# Conn_pcb1.net
KiCad netlist of a schematic drawn in EAGLE
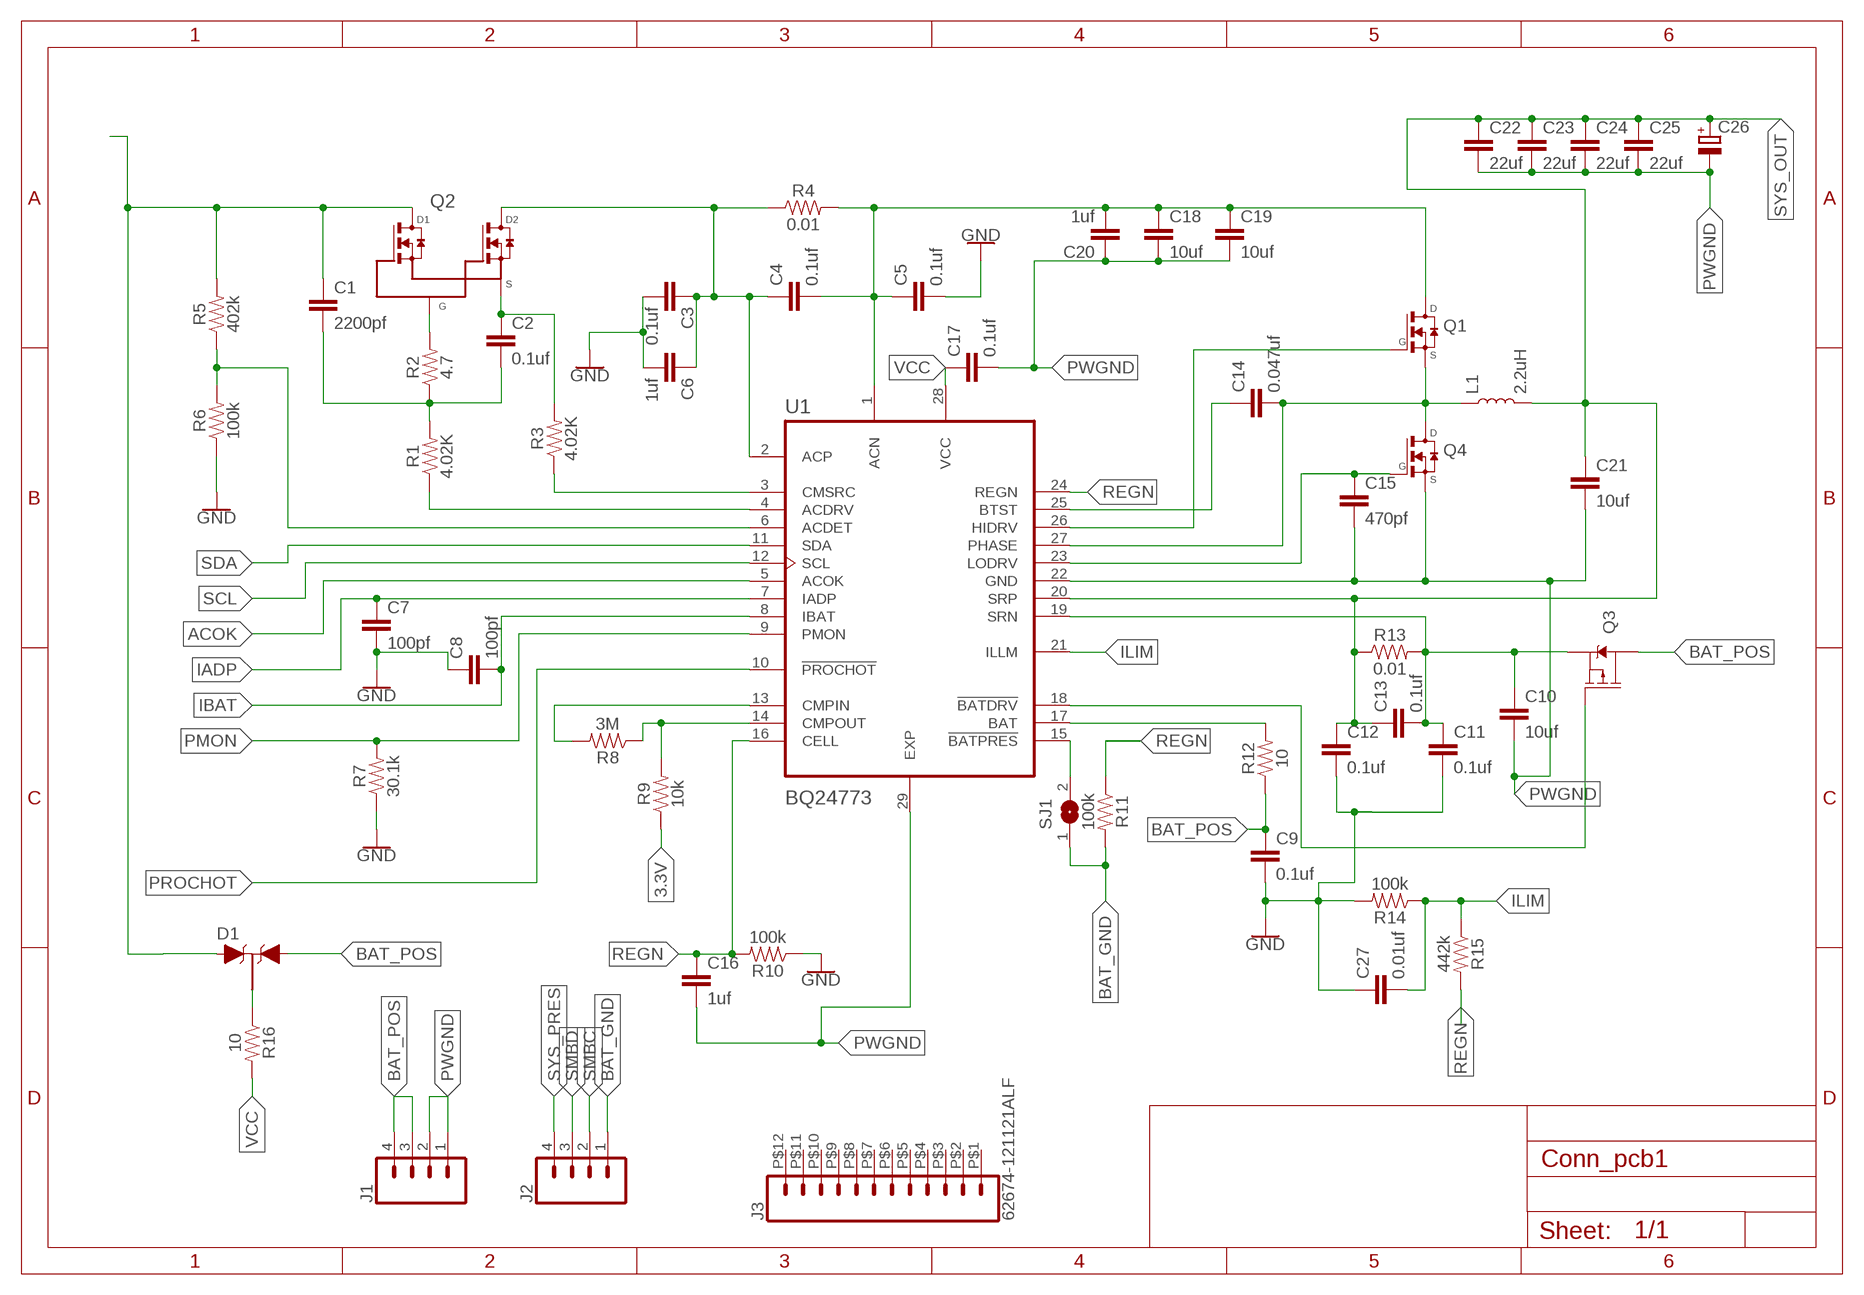
[diagram p0: schematic, sheet 1]

(export (version "E")
  (design (tool "Eeschema 10.0.6"))
  (components
    (comp (ref "C1")
      (value "2200pf")
      (footprint "eagle-import:CAPC1005X50")
      (libsource (lib "eagle-import") (part "CAP0402"))
    )
    (comp (ref "C2")
      (value "0.1uf")
      (footprint "eagle-import:CAPC1005X50")
      (libsource (lib "eagle-import") (part "CAP0402"))
    )
    (comp (ref "C3")
      (value "0.1uf")
      (footprint "eagle-import:CAPC1005X50")
      (libsource (lib "eagle-import") (part "CAP0402"))
    )
    (comp (ref "C4")
      (value "0.1uf")
      (footprint "eagle-import:CAPC1005X50")
      (libsource (lib "eagle-import") (part "CAP0402"))
    )
    (comp (ref "C5")
      (value "0.1uf")
      (footprint "eagle-import:CAPC1005X50")
      (libsource (lib "eagle-import") (part "CAP0402"))
    )
    (comp (ref "C6")
      (value "1uf")
      (footprint "eagle-import:CAPC1005X50")
      (libsource (lib "eagle-import") (part "CAP0402"))
    )
    (comp (ref "C7")
      (value "100pf")
      (footprint "eagle-import:CAPC1005X50")
      (libsource (lib "eagle-import") (part "CAP0402"))
    )
    (comp (ref "C8")
      (value "100pf")
      (footprint "eagle-import:CAPC1005X50")
      (libsource (lib "eagle-import") (part "CAP0402"))
    )
    (comp (ref "C9")
      (value "0.1uf")
      (footprint "eagle-import:CAPC1005X50")
      (libsource (lib "eagle-import") (part "CAP0402"))
    )
    (comp (ref "C10")
      (value "10uf")
      (footprint "eagle-import:C0805K")
      (libsource (lib "eagle-import") (part "C-EUC0805K"))
    )
    (comp (ref "C11")
      (value "0.1uf")
      (footprint "eagle-import:CAPC1005X50")
      (libsource (lib "eagle-import") (part "CAP0402"))
    )
    (comp (ref "C12")
      (value "0.1uf")
      (footprint "eagle-import:CAPC1005X50")
      (libsource (lib "eagle-import") (part "CAP0402"))
    )
    (comp (ref "C13")
      (value "0.1uf")
      (footprint "eagle-import:CAPC1005X50")
      (libsource (lib "eagle-import") (part "CAP0402"))
    )
    (comp (ref "C14")
      (value "0.047uf")
      (footprint "eagle-import:CAPC1005X50")
      (libsource (lib "eagle-import") (part "CAP0402"))
    )
    (comp (ref "C15")
      (value "470pf")
      (footprint "eagle-import:CAPC1005X50")
      (libsource (lib "eagle-import") (part "CAP0402"))
    )
    (comp (ref "C16")
      (value "1uf")
      (footprint "eagle-import:CAPC1005X50")
      (libsource (lib "eagle-import") (part "CAP0402"))
    )
    (comp (ref "C17")
      (value "0.1uf")
      (footprint "eagle-import:CAPC1005X50")
      (libsource (lib "eagle-import") (part "CAP0402"))
    )
    (comp (ref "C18")
      (value "10uf")
      (footprint "eagle-import:C0805K")
      (libsource (lib "eagle-import") (part "C-EUC0805K"))
    )
    (comp (ref "C19")
      (value "10uf")
      (footprint "eagle-import:C0805K")
      (libsource (lib "eagle-import") (part "C-EUC0805K"))
    )
    (comp (ref "C20")
      (value "1uf")
      (footprint "eagle-import:CAPC1005X50")
      (libsource (lib "eagle-import") (part "CAP0402"))
    )
    (comp (ref "C21")
      (value "10uf")
      (footprint "eagle-import:C0805K")
      (libsource (lib "eagle-import") (part "C-EUC0805K"))
    )
    (comp (ref "C22")
      (value "22uf")
      (footprint "eagle-import:C1206")
      (libsource (lib "eagle-import") (part "C-EUC1206"))
    )
    (comp (ref "C23")
      (value "22uf")
      (footprint "eagle-import:C1206")
      (libsource (lib "eagle-import") (part "C-EUC1206"))
    )
    (comp (ref "C24")
      (value "22uf")
      (footprint "eagle-import:C1206")
      (libsource (lib "eagle-import") (part "C-EUC1206"))
    )
    (comp (ref "C25")
      (value "22uf")
      (footprint "eagle-import:C1206")
      (libsource (lib "eagle-import") (part "C-EUC1206"))
    )
    (comp (ref "C26")
      (value "CPOL-EUF")
      (footprint "eagle-import:PANASONIC_F")
      (libsource (lib "eagle-import") (part "CPOL-EUF"))
    )
    (comp (ref "C27")
      (value "0.01uf")
      (footprint "eagle-import:CAPC1005X50")
      (libsource (lib "eagle-import") (part "CAP0402"))
    )
    (comp (ref "D1")
      (value "BAT54C-7-F")
      (footprint "eagle-import:SOT95P235X110-3")
      (libsource (lib "eagle-import") (part "BAT54C-7-F"))
    )
    (comp (ref "J1")
      (value "CONN_041.3")
      (footprint "eagle-import:1X04_NO_SILK_1.3")
      (libsource (lib "eagle-import") (part "CONN_041.3"))
    )
    (comp (ref "J2")
      (value "CONN_041.3")
      (footprint "eagle-import:1X04_NO_SILK_1.3")
      (libsource (lib "eagle-import") (part "CONN_041.3"))
    )
    (comp (ref "J3")
      (value "62674-121121ALF")
      (footprint "eagle-import:62674-121121ALF")
      (libsource (lib "eagle-import") (part "62674-121121ALF"))
    )
    (comp (ref "L1")
      (value "2.2uH")
      (footprint "eagle-import:RESM6365X610")
      (libsource (lib "eagle-import") (part "XEL6060-222MEB"))
    )
    (comp (ref "Q1")
      (value "CSD17308Q3")
      (footprint "eagle-import:SON65P330X330X110-8")
      (fields (field (name "SPICEPREFIX") "Q"))
      (libsource (lib "eagle-import") (part "CSD17308Q3"))
    )
    (comp (ref "Q2")
      (value "CSD87312Q3EVSON")
      (footprint "eagle-import:QFN65P330X330X100-12")
      (libsource (lib "eagle-import") (part "CSD87312Q3EVSON"))
    )
    (comp (ref "Q3")
      (value "CSD25402Q3A")
      (footprint "eagle-import:CSD25402Q3A")
      (libsource (lib "eagle-import") (part "CSD25402Q3A"))
    )
    (comp (ref "Q4")
      (value "CSD17308Q3")
      (footprint "eagle-import:SON65P330X330X110-8")
      (fields (field (name "SPICEPREFIX") "Q"))
      (libsource (lib "eagle-import") (part "CSD17308Q3"))
    )
    (comp (ref "R1")
      (value "4.02K")
      (footprint "eagle-import:0402")
      (libsource (lib "eagle-import") (part "RES4K04020402"))
    )
    (comp (ref "R2")
      (value "4.7")
      (footprint "eagle-import:0402")
      (libsource (lib "eagle-import") (part "RES4K04020402"))
    )
    (comp (ref "R3")
      (value "4.02K")
      (footprint "eagle-import:0402")
      (libsource (lib "eagle-import") (part "RES4K04020402"))
    )
    (comp (ref "R4")
      (value "0.01")
      (footprint "eagle-import:1206")
      (libsource (lib "eagle-import") (part "SENSE-RES"))
    )
    (comp (ref "R5")
      (value "402k")
      (footprint "eagle-import:0402")
      (libsource (lib "eagle-import") (part "RES4K04020402"))
    )
    (comp (ref "R6")
      (value "100k")
      (footprint "eagle-import:0402")
      (libsource (lib "eagle-import") (part "RES4K04020402"))
    )
    (comp (ref "R7")
      (value "30.1k")
      (footprint "eagle-import:0402")
      (libsource (lib "eagle-import") (part "RES4K04020402"))
    )
    (comp (ref "R8")
      (value "3M")
      (footprint "eagle-import:0402")
      (libsource (lib "eagle-import") (part "RES4K04020402"))
    )
    (comp (ref "R9")
      (value "10k")
      (footprint "eagle-import:0402")
      (libsource (lib "eagle-import") (part "RES4K04020402"))
    )
    (comp (ref "R10")
      (value "100k")
      (footprint "eagle-import:0402")
      (libsource (lib "eagle-import") (part "RES4K04020402"))
    )
    (comp (ref "R11")
      (value "100k")
      (footprint "eagle-import:0402")
      (libsource (lib "eagle-import") (part "RES4K04020402"))
    )
    (comp (ref "R12")
      (value "10")
      (footprint "eagle-import:0402")
      (libsource (lib "eagle-import") (part "RES4K04020402"))
    )
    (comp (ref "R13")
      (value "0.01")
      (footprint "eagle-import:1206")
      (libsource (lib "eagle-import") (part "SENSE-RES"))
    )
    (comp (ref "R14")
      (value "100k")
      (footprint "eagle-import:0402")
      (libsource (lib "eagle-import") (part "RES4K04020402"))
    )
    (comp (ref "R15")
      (value "442k")
      (footprint "eagle-import:0402")
      (libsource (lib "eagle-import") (part "RES4K04020402"))
    )
    (comp (ref "R16")
      (value "10")
      (footprint "eagle-import:0402")
      (libsource (lib "eagle-import") (part "RES4K04020402"))
    )
    (comp (ref "SJ1") (value "SJ") (footprint "eagle-import:SJ") (libsource (lib "eagle-import") (part "SJ")))
    (comp (ref "U1")
      (value "BQ24773")
      (footprint "eagle-import:QFN40P400X400X80-29T240")
      (libsource (lib "eagle-import") (part "BQ24773"))
    )
  )
  (nets
    (net (code "1") (name "3.3V") (class "Default")
      (node (ref "R9") (pin "1") (pinfunction "1_1") (pintype "passive"))
    )
    (net (code "2") (name "ACOK") (class "Default")
      (node (ref "U1") (pin "5") (pinfunction "ACOK_5") (pintype "output"))
    )
    (net (code "3") (name "BAT_GND") (class "Default")
      (node (ref "J2") (pin "1") (pinfunction "1_1") (pintype "passive"))
      (node (ref "R11") (pin "2") (pinfunction "2_2") (pintype "passive"))
      (node (ref "SJ1") (pin "1") (pinfunction "1_1") (pintype "passive"))
    )
    (net (code "4") (name "BAT_POS") (class "Default")
      (node (ref "C9") (pin "1") (pinfunction "1_1") (pintype "passive"))
      (node (ref "D1") (pin "2") (pinfunction "A2_2") (pintype "passive"))
      (node (ref "J1") (pin "3") (pinfunction "3_3") (pintype "passive"))
      (node (ref "J1") (pin "4") (pinfunction "4_4") (pintype "passive"))
      (node (ref "Q3") (pin "1") (pinfunction "D_1") (pintype "bidirectional"))
      (node (ref "Q3") (pin "2") (pinfunction "D_2") (pintype "bidirectional"))
      (node (ref "Q3") (pin "3") (pinfunction "D_3") (pintype "bidirectional"))
      (node (ref "R12") (pin "1") (pinfunction "1_1") (pintype "passive"))
    )
    (net (code "5") (name "GND") (class "Default")
      (node (ref "C11") (pin "2") (pinfunction "2_2") (pintype "passive"))
      (node (ref "C12") (pin "2") (pinfunction "2_2") (pintype "passive"))
      (node (ref "C27") (pin "1") (pinfunction "1_1") (pintype "passive"))
      (node (ref "C3") (pin "2") (pinfunction "2_2") (pintype "passive"))
      (node (ref "C5") (pin "2") (pinfunction "2_2") (pintype "passive"))
      (node (ref "C6") (pin "2") (pinfunction "2_2") (pintype "passive"))
      (node (ref "C7") (pin "2") (pinfunction "2_2") (pintype "passive"))
      (node (ref "C8") (pin "1") (pinfunction "1_1") (pintype "passive"))
      (node (ref "C9") (pin "2") (pinfunction "2_2") (pintype "passive"))
      (node (ref "R10") (pin "1") (pinfunction "1_1") (pintype "passive"))
      (node (ref "R14") (pin "2") (pinfunction "2_2") (pintype "passive"))
      (node (ref "R6") (pin "1") (pinfunction "1_1") (pintype "passive"))
      (node (ref "R7") (pin "1") (pinfunction "1_1") (pintype "passive"))
    )
    (net (code "6") (name "IADP") (class "Default")
      (node (ref "C7") (pin "1") (pinfunction "1_1") (pintype "passive"))
      (node (ref "U1") (pin "7") (pinfunction "IADP_7") (pintype "output"))
    )
    (net (code "7") (name "IBAT") (class "Default")
      (node (ref "C8") (pin "2") (pinfunction "2_2") (pintype "passive"))
      (node (ref "U1") (pin "8") (pinfunction "IBAT_8") (pintype "output"))
    )
    (net (code "8") (name "ILIM") (class "Default")
      (node (ref "C27") (pin "2") (pinfunction "2_2") (pintype "passive"))
      (node (ref "R14") (pin "1") (pinfunction "1_1") (pintype "passive"))
      (node (ref "R15") (pin "1") (pinfunction "1_1") (pintype "passive"))
      (node (ref "U1") (pin "21") (pinfunction "ILLM_21") (pintype "input"))
    )
    (net (code "9") (name "Net-(C1-Pad2)") (class "Default")
      (node (ref "C1") (pin "2") (pinfunction "2_2") (pintype "passive"))
      (node (ref "C2") (pin "2") (pinfunction "2_2") (pintype "passive"))
      (node (ref "R1") (pin "2") (pinfunction "2_2") (pintype "passive"))
      (node (ref "R2") (pin "1") (pinfunction "1_1") (pintype "passive"))
    )
    (net (code "10") (name "Net-(C2-Pad1)") (class "Default")
      (node (ref "C2") (pin "1") (pinfunction "1_1") (pintype "passive"))
      (node (ref "Q2") (pin "9") (pinfunction "S_9") (pintype "passive"))
      (node (ref "Q2") (pin "9.1") (pinfunction "S_9.1") (pintype "passive"))
      (node (ref "Q2") (pin "9.2") (pinfunction "S_9.2") (pintype "passive"))
      (node (ref "Q2") (pin "9.3") (pinfunction "S_9.3") (pintype "passive"))
      (node (ref "Q2") (pin "9.4") (pinfunction "S_9.4") (pintype "passive"))
      (node (ref "R3") (pin "2") (pinfunction "2_2") (pintype "passive"))
    )
    (net (code "11") (name "Net-(D1-A1)") (class "Default")
      (node (ref "C1") (pin "1") (pinfunction "1_1") (pintype "passive"))
      (node (ref "D1") (pin "1") (pinfunction "A1_1") (pintype "passive"))
      (node (ref "Q2") (pin "1") (pinfunction "D1_1") (pintype "passive"))
      (node (ref "Q2") (pin "3") (pinfunction "D1_3") (pintype "passive"))
      (node (ref "Q2") (pin "4") (pinfunction "D1_4") (pintype "passive"))
      (node (ref "R5") (pin "2") (pinfunction "2_2") (pintype "passive"))
    )
    (net (code "12") (name "Net-(D1-K)") (class "Default")
      (node (ref "D1") (pin "3") (pinfunction "K_3") (pintype "passive"))
      (node (ref "R16") (pin "1") (pinfunction "1_1") (pintype "passive"))
    )
    (net (code "13") (name "Net-(Q1-G)") (class "Default")
      (node (ref "Q1") (pin "4") (pinfunction "G_4") (pintype "passive"))
      (node (ref "U1") (pin "26") (pinfunction "HIDRV_26") (pintype "output"))
    )
    (net (code "14") (name "Net-(Q2-G)") (class "Default")
      (node (ref "Q2") (pin "5") (pinfunction "G_5") (pintype "passive"))
      (node (ref "R2") (pin "2") (pinfunction "2_2") (pintype "passive"))
    )
    (net (code "15") (name "Net-(Q3-G)") (class "Default")
      (node (ref "Q3") (pin "4") (pinfunction "G_4") (pintype "bidirectional"))
      (node (ref "U1") (pin "18") (pinfunction "~{BATDRV}_18") (pintype "output"))
    )
    (net (code "16") (name "Net-(Q4-G)") (class "Default")
      (node (ref "C15") (pin "1") (pinfunction "1_1") (pintype "passive"))
      (node (ref "Q4") (pin "4") (pinfunction "G_4") (pintype "passive"))
      (node (ref "U1") (pin "23") (pinfunction "LODRV_23") (pintype "output"))
    )
    (net (code "17") (name "Net-(U1-ACDET)") (class "Default")
      (node (ref "R5") (pin "1") (pinfunction "1_1") (pintype "passive"))
      (node (ref "R6") (pin "2") (pinfunction "2_2") (pintype "passive"))
      (node (ref "U1") (pin "6") (pinfunction "ACDET_6") (pintype "input"))
    )
    (net (code "18") (name "Net-(U1-ACDRV)") (class "Default")
      (node (ref "R1") (pin "1") (pinfunction "1_1") (pintype "passive"))
      (node (ref "U1") (pin "4") (pinfunction "ACDRV_4") (pintype "output"))
    )
    (net (code "19") (name "Net-(U1-ACN)") (class "Default")
      (node (ref "C18") (pin "1") (pinfunction "1_1") (pintype "passive"))
      (node (ref "C19") (pin "1") (pinfunction "1_1") (pintype "passive"))
      (node (ref "C20") (pin "2") (pinfunction "2_2") (pintype "passive"))
      (node (ref "C4") (pin "2") (pinfunction "2_2") (pintype "passive"))
      (node (ref "C5") (pin "1") (pinfunction "1_1") (pintype "passive"))
      (node (ref "Q1") (pin "5") (pinfunction "D_5") (pintype "passive"))
      (node (ref "Q1") (pin "6") (pinfunction "D_6") (pintype "passive"))
      (node (ref "Q1") (pin "7") (pinfunction "D_7") (pintype "passive"))
      (node (ref "Q1") (pin "8") (pinfunction "D_8") (pintype "passive"))
      (node (ref "R4") (pin "2") (pinfunction "2_2") (pintype "passive"))
      (node (ref "U1") (pin "1") (pinfunction "ACN_1") (pintype "input"))
    )
    (net (code "20") (name "Net-(U1-ACP)") (class "Default")
      (node (ref "C3") (pin "1") (pinfunction "1_1") (pintype "passive"))
      (node (ref "C4") (pin "1") (pinfunction "1_1") (pintype "passive"))
      (node (ref "C6") (pin "1") (pinfunction "1_1") (pintype "passive"))
      (node (ref "Q2") (pin "6") (pinfunction "D2_6") (pintype "passive"))
      (node (ref "Q2") (pin "7") (pinfunction "D2_7") (pintype "passive"))
      (node (ref "Q2") (pin "8") (pinfunction "D2_8") (pintype "passive"))
      (node (ref "R4") (pin "1") (pinfunction "1_1") (pintype "passive"))
      (node (ref "U1") (pin "2") (pinfunction "ACP_2") (pintype "input"))
    )
    (net (code "21") (name "Net-(U1-BAT)") (class "Default")
      (node (ref "R12") (pin "2") (pinfunction "2_2") (pintype "passive"))
      (node (ref "U1") (pin "17") (pinfunction "BAT_17") (pintype "input"))
    )
    (net (code "22") (name "Net-(U1-BTST)") (class "Default")
      (node (ref "C14") (pin "1") (pinfunction "1_1") (pintype "passive"))
      (node (ref "U1") (pin "25") (pinfunction "BTST_25") (pintype "passive"))
    )
    (net (code "23") (name "Net-(U1-CMPIN)") (class "Default")
      (node (ref "R8") (pin "2") (pinfunction "2_2") (pintype "passive"))
      (node (ref "U1") (pin "13") (pinfunction "CMPIN_13") (pintype "input"))
    )
    (net (code "24") (name "Net-(U1-CMPOUT)") (class "Default")
      (node (ref "R8") (pin "1") (pinfunction "1_1") (pintype "passive"))
      (node (ref "R9") (pin "2") (pinfunction "2_2") (pintype "passive"))
      (node (ref "U1") (pin "14") (pinfunction "CMPOUT_14") (pintype "output"))
    )
    (net (code "25") (name "Net-(U1-CMSRC)") (class "Default")
      (node (ref "R3") (pin "1") (pinfunction "1_1") (pintype "passive"))
      (node (ref "U1") (pin "3") (pinfunction "CMSRC_3") (pintype "input"))
    )
    (net (code "26") (name "Net-(U1-PHASE)") (class "Default")
      (node (ref "C14") (pin "2") (pinfunction "2_2") (pintype "passive"))
      (node (ref "L1") (pin "1") (pinfunction "1_1") (pintype "passive"))
      (node (ref "Q1") (pin "1") (pinfunction "S_1") (pintype "passive"))
      (node (ref "Q1") (pin "2") (pinfunction "S_2") (pintype "passive"))
      (node (ref "Q1") (pin "3") (pinfunction "S_3") (pintype "passive"))
      (node (ref "Q4") (pin "5") (pinfunction "D_5") (pintype "passive"))
      (node (ref "Q4") (pin "6") (pinfunction "D_6") (pintype "passive"))
      (node (ref "Q4") (pin "7") (pinfunction "D_7") (pintype "passive"))
      (node (ref "Q4") (pin "8") (pinfunction "D_8") (pintype "passive"))
      (node (ref "U1") (pin "27") (pinfunction "PHASE_27") (pintype "output"))
    )
    (net (code "27") (name "Net-(U1-SRN)") (class "Default")
      (node (ref "C10") (pin "1") (pinfunction "1_1") (pintype "passive"))
      (node (ref "C11") (pin "1") (pinfunction "1_1") (pintype "passive"))
      (node (ref "C13") (pin "2") (pinfunction "2_2") (pintype "passive"))
      (node (ref "Q3") (pin "5") (pinfunction "S_5") (pintype "bidirectional"))
      (node (ref "Q3") (pin "6") (pinfunction "S_6") (pintype "bidirectional"))
      (node (ref "Q3") (pin "7") (pinfunction "S_7") (pintype "bidirectional"))
      (node (ref "Q3") (pin "8") (pinfunction "S_8") (pintype "bidirectional"))
      (node (ref "Q3") (pin "9") (pinfunction "S_9") (pintype "bidirectional"))
      (node (ref "R13") (pin "2") (pinfunction "2_2") (pintype "passive"))
      (node (ref "U1") (pin "19") (pinfunction "SRN_19") (pintype "input"))
    )
    (net (code "28") (name "Net-(U1-~{BATPRES})") (class "Default")
      (node (ref "SJ1") (pin "2") (pinfunction "2_2") (pintype "passive"))
      (node (ref "U1") (pin "15") (pinfunction "~{BATPRES}_15") (pintype "input"))
    )
    (net (code "29") (name "PMON") (class "Default")
      (node (ref "R7") (pin "2") (pinfunction "2_2") (pintype "passive"))
      (node (ref "U1") (pin "9") (pinfunction "PMON_9") (pintype "output"))
    )
    (net (code "30") (name "PROCHOT") (class "Default")
      (node (ref "U1") (pin "10") (pinfunction "~{PROCHOT}_10") (pintype "output"))
    )
    (net (code "31") (name "PWGND") (class "Default")
      (node (ref "C10") (pin "2") (pinfunction "2_2") (pintype "passive"))
      (node (ref "C15") (pin "2") (pinfunction "2_2") (pintype "passive"))
      (node (ref "C16") (pin "2") (pinfunction "2_2") (pintype "passive"))
      (node (ref "C17") (pin "2") (pinfunction "2_2") (pintype "passive"))
      (node (ref "C18") (pin "2") (pinfunction "2_2") (pintype "passive"))
      (node (ref "C19") (pin "2") (pinfunction "2_2") (pintype "passive"))
      (node (ref "C20") (pin "1") (pinfunction "1_1") (pintype "passive"))
      (node (ref "C21") (pin "2") (pinfunction "2_2") (pintype "passive"))
      (node (ref "C22") (pin "2") (pinfunction "2_2") (pintype "passive"))
      (node (ref "C23") (pin "2") (pinfunction "2_2") (pintype "passive"))
      (node (ref "C24") (pin "2") (pinfunction "2_2") (pintype "passive"))
      (node (ref "C25") (pin "2") (pinfunction "2_2") (pintype "passive"))
      (node (ref "C26") (pin "-") (pinfunction "-_-") (pintype "passive"))
      (node (ref "J1") (pin "1") (pinfunction "1_1") (pintype "passive"))
      (node (ref "J1") (pin "2") (pinfunction "2_2") (pintype "passive"))
      (node (ref "Q4") (pin "1") (pinfunction "S_1") (pintype "passive"))
      (node (ref "Q4") (pin "2") (pinfunction "S_2") (pintype "passive"))
      (node (ref "Q4") (pin "3") (pinfunction "S_3") (pintype "passive"))
      (node (ref "U1") (pin "22") (pinfunction "GND_22") (pintype "power_in"))
      (node (ref "U1") (pin "29") (pinfunction "EXP_29") (pintype "power_in"))
    )
    (net (code "32") (name "REGN") (class "Default")
      (node (ref "C16") (pin "1") (pinfunction "1_1") (pintype "passive"))
      (node (ref "R10") (pin "2") (pinfunction "2_2") (pintype "passive"))
      (node (ref "R11") (pin "1") (pinfunction "1_1") (pintype "passive"))
      (node (ref "R15") (pin "2") (pinfunction "2_2") (pintype "passive"))
      (node (ref "U1") (pin "16") (pinfunction "CELL_16") (pintype "input"))
      (node (ref "U1") (pin "24") (pinfunction "REGN_24") (pintype "output"))
    )
    (net (code "33") (name "SCL") (class "Default")
      (node (ref "U1") (pin "12") (pinfunction "SCL_12") (pintype "input"))
    )
    (net (code "34") (name "SDA") (class "Default")
      (node (ref "U1") (pin "11") (pinfunction "SDA_11") (pintype "bidirectional"))
    )
    (net (code "35") (name "SMBC") (class "Default")
      (node (ref "J2") (pin "2") (pinfunction "2_2") (pintype "passive"))
    )
    (net (code "36") (name "SMBD") (class "Default")
      (node (ref "J2") (pin "3") (pinfunction "3_3") (pintype "passive"))
    )
    (net (code "37") (name "SYS_OUT") (class "Default")
      (node (ref "C12") (pin "1") (pinfunction "1_1") (pintype "passive"))
      (node (ref "C13") (pin "1") (pinfunction "1_1") (pintype "passive"))
      (node (ref "C21") (pin "1") (pinfunction "1_1") (pintype "passive"))
      (node (ref "C22") (pin "1") (pinfunction "1_1") (pintype "passive"))
      (node (ref "C23") (pin "1") (pinfunction "1_1") (pintype "passive"))
      (node (ref "C24") (pin "1") (pinfunction "1_1") (pintype "passive"))
      (node (ref "C25") (pin "1") (pinfunction "1_1") (pintype "passive"))
      (node (ref "C26") (pin "+") (pinfunction "+_+") (pintype "passive"))
      (node (ref "L1") (pin "2") (pinfunction "2_2") (pintype "passive"))
      (node (ref "R13") (pin "1") (pinfunction "1_1") (pintype "passive"))
      (node (ref "U1") (pin "20") (pinfunction "SRP_20") (pintype "input"))
    )
    (net (code "38") (name "SYS_PRES") (class "Default")
      (node (ref "J2") (pin "4") (pinfunction "4_4") (pintype "passive"))
    )
    (net (code "39") (name "VCC") (class "Default")
      (node (ref "C17") (pin "1") (pinfunction "1_1") (pintype "passive"))
      (node (ref "R16") (pin "2") (pinfunction "2_2") (pintype "passive"))
      (node (ref "U1") (pin "28") (pinfunction "VCC_28") (pintype "power_in"))
    )
    (net (code "40") (name "unconnected-(J3-1-PadP$1)") (class "Default")
      (node (ref "J3") (pin "P$1") (pinfunction "1_P$1") (pintype "passive"))
    )
    (net (code "41") (name "unconnected-(J3-2-PadP$2)") (class "Default")
      (node (ref "J3") (pin "P$2") (pinfunction "2_P$2") (pintype "passive"))
    )
    (net (code "42") (name "unconnected-(J3-3-PadP$3)") (class "Default")
      (node (ref "J3") (pin "P$3") (pinfunction "3_P$3") (pintype "passive"))
    )
    (net (code "43") (name "unconnected-(J3-4-PadP$4)") (class "Default")
      (node (ref "J3") (pin "P$4") (pinfunction "4_P$4") (pintype "passive"))
    )
    (net (code "44") (name "unconnected-(J3-5-PadP$5)") (class "Default")
      (node (ref "J3") (pin "P$5") (pinfunction "5_P$5") (pintype "passive"))
    )
    (net (code "45") (name "unconnected-(J3-6-PadP$6)") (class "Default")
      (node (ref "J3") (pin "P$6") (pinfunction "6_P$6") (pintype "passive"))
    )
    (net (code "46") (name "unconnected-(J3-7-PadP$7)") (class "Default")
      (node (ref "J3") (pin "P$7") (pinfunction "7_P$7") (pintype "passive"))
    )
    (net (code "47") (name "unconnected-(J3-8-PadP$8)") (class "Default")
      (node (ref "J3") (pin "P$8") (pinfunction "8_P$8") (pintype "passive"))
    )
    (net (code "48") (name "unconnected-(J3-9-PadP$9)") (class "Default")
      (node (ref "J3") (pin "P$9") (pinfunction "9_P$9") (pintype "passive"))
    )
    (net (code "49") (name "unconnected-(J3-10-PadP$10)") (class "Default")
      (node (ref "J3") (pin "P$10") (pinfunction "10_P$10") (pintype "passive"))
    )
    (net (code "50") (name "unconnected-(J3-11-PadP$11)") (class "Default")
      (node (ref "J3") (pin "P$11") (pinfunction "11_P$11") (pintype "passive"))
    )
    (net (code "51") (name "unconnected-(J3-12-PadP$12)") (class "Default")
      (node (ref "J3") (pin "P$12") (pinfunction "12_P$12") (pintype "passive"))
    )
  )
)
